# Stacja_Lutownicza_STM.net
KiCad netlist of a schematic drawn in EAGLE
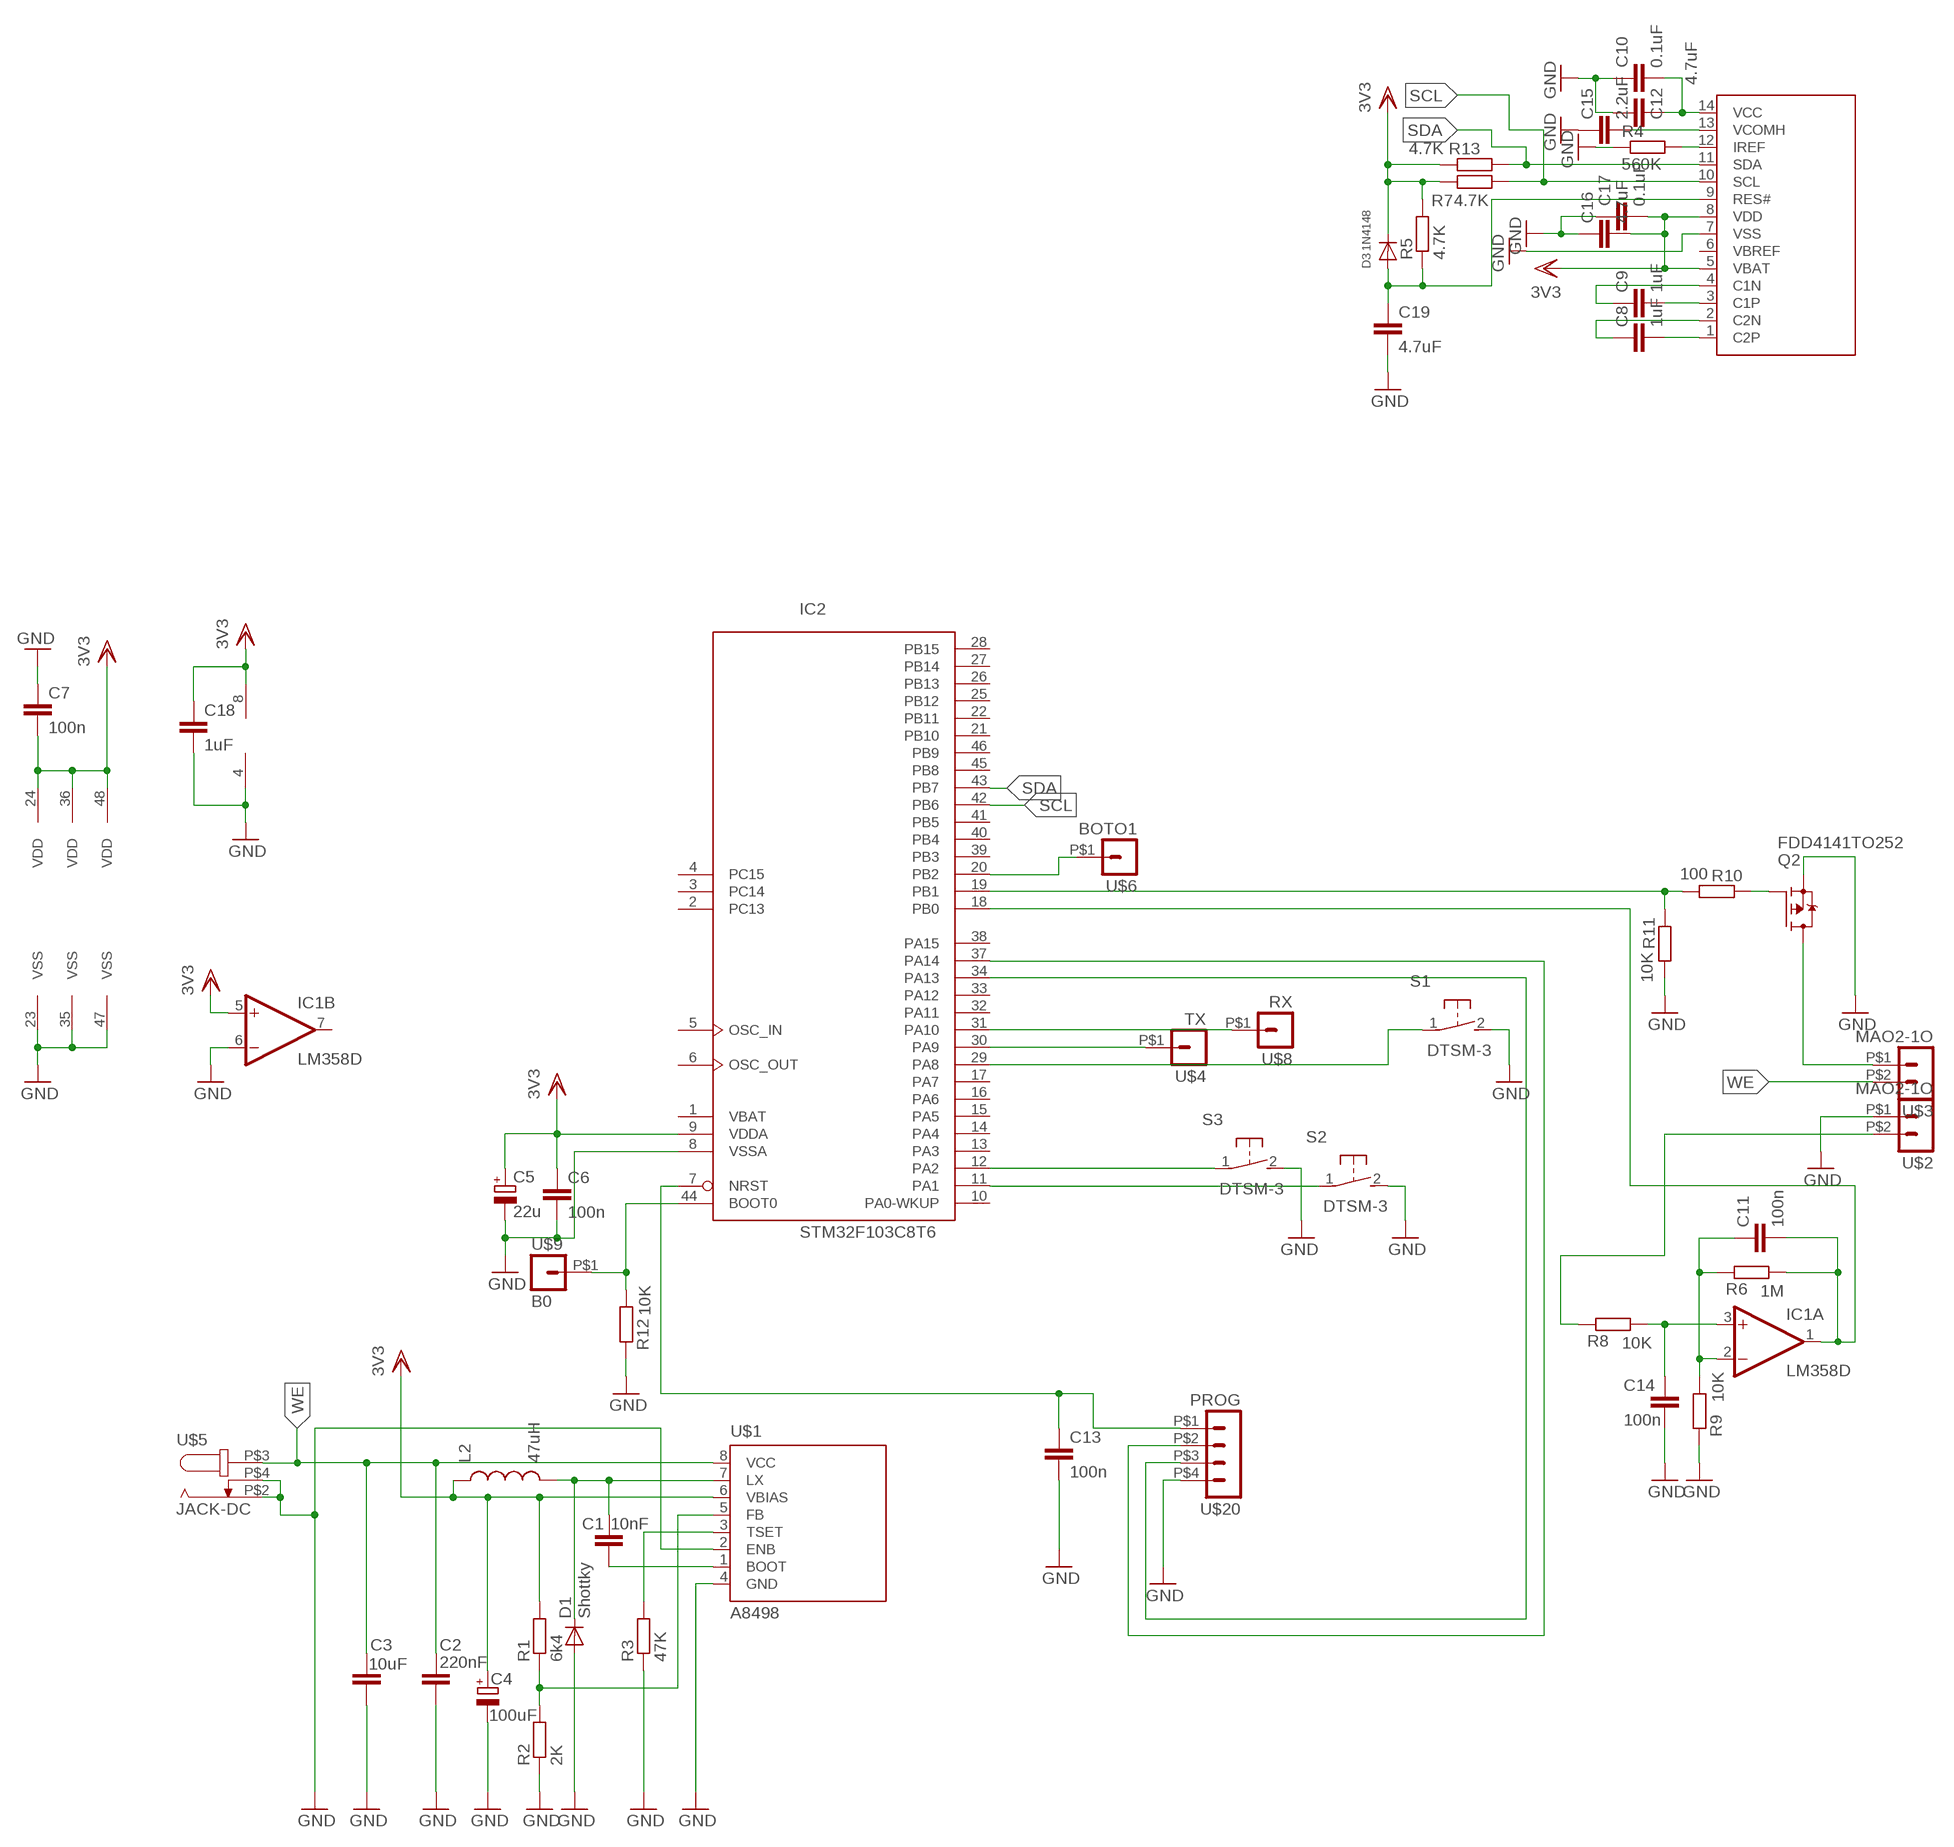
[diagram p0: schematic, sheet 1]

(export (version "E")
  (design (tool "Eeschema 10.0.6"))
  (components
    (comp (ref "C1")
      (value "10nF")
      (footprint "eagle-import:C1206")
      (libsource (lib "eagle-import") (part "C-EUC1206"))
    )
    (comp (ref "C2")
      (value "220nF")
      (footprint "eagle-import:C1210")
      (libsource (lib "eagle-import") (part "C-EUC1210"))
    )
    (comp (ref "C3")
      (value "10uF")
      (footprint "eagle-import:C0603")
      (libsource (lib "eagle-import") (part "C-EUC0603"))
    )
    (comp (ref "C4")
      (value "100uF")
      (footprint "eagle-import:SMC_D")
      (libsource (lib "eagle-import") (part "CPOL-EUSMCD"))
    )
    (comp (ref "C5")
      (value "22u")
      (footprint "eagle-import:R_2012-12R")
      (libsource (lib "eagle-import") (part "resistor_CPOL-EUR/2012-12R"))
    )
    (comp (ref "C6")
      (value "100n")
      (footprint "eagle-import:C0603")
      (libsource (lib "eagle-import") (part "resistor_C-EUC0603"))
    )
    (comp (ref "C7")
      (value "100n")
      (footprint "eagle-import:C0603")
      (libsource (lib "eagle-import") (part "resistor_C-EUC0603"))
    )
    (comp (ref "C8")
      (value "1uF")
      (footprint "eagle-import:C0603")
      (libsource (lib "eagle-import") (part "C-EUC0603"))
    )
    (comp (ref "C9")
      (value "1uF")
      (footprint "eagle-import:C0603")
      (libsource (lib "eagle-import") (part "C-EUC0603"))
    )
    (comp (ref "C10")
      (value "0.1uF")
      (footprint "eagle-import:C0603")
      (libsource (lib "eagle-import") (part "C-EUC0603"))
    )
    (comp (ref "C11")
      (value "100n")
      (footprint "eagle-import:C0603")
      (libsource (lib "eagle-import") (part "resistor_C-EUC0603"))
    )
    (comp (ref "C12")
      (value "4.7uF")
      (footprint "eagle-import:C0603")
      (libsource (lib "eagle-import") (part "C-EUC0603"))
    )
    (comp (ref "C13")
      (value "100n")
      (footprint "eagle-import:C0603")
      (libsource (lib "eagle-import") (part "resistor_C-EUC0603"))
    )
    (comp (ref "C14")
      (value "100n")
      (footprint "eagle-import:C0603")
      (libsource (lib "eagle-import") (part "resistor_C-EUC0603"))
    )
    (comp (ref "C15")
      (value "2.2uF")
      (footprint "eagle-import:C0603")
      (libsource (lib "eagle-import") (part "C-EUC0603"))
    )
    (comp (ref "C16")
      (value "4.7uF")
      (footprint "eagle-import:C0603")
      (libsource (lib "eagle-import") (part "C-EUC0603"))
    )
    (comp (ref "C17")
      (value "0.1uF")
      (footprint "eagle-import:C0603")
      (libsource (lib "eagle-import") (part "C-EUC0603"))
    )
    (comp (ref "C18")
      (value "1uF")
      (footprint "eagle-import:C0603")
      (libsource (lib "eagle-import") (part "C-EUC0603"))
    )
    (comp (ref "C19")
      (value "4.7uF")
      (footprint "eagle-import:C0603")
      (libsource (lib "eagle-import") (part "C-EUC0603"))
    )
    (comp (ref "D1")
      (value "Shottky")
      (footprint "eagle-import:SOD-123_MINI-SMA")
      (libsource (lib "eagle-import") (part "CGRM400-G3"))
    )
    (comp (ref "D3")
      (value "1N4148")
      (footprint "eagle-import:SOD-323F")
      (libsource (lib "eagle-import") (part "DIODESOD-323F"))
    )
    (comp (ref "IC1")
      (value "LM358D")
      (footprint "eagle-import:SO08")
      (libsource (lib "eagle-import") (part "LM358D"))
    )
    (comp (ref "IC2")
      (value "STM32F103C8T6")
      (footprint "eagle-import:LQFP48")
      (libsource (lib "eagle-import") (part "STM32F102CT4"))
    )
    (comp (ref "L2")
      (value "47uH")
      (footprint "eagle-import:INDUCTOR-1206")
      (libsource (lib "eagle-import") (part "INDUCTORH1206"))
    )
    (comp (ref "Q2")
      (value "FDD4141TO252")
      (footprint "eagle-import:TO252")
      (libsource (lib "eagle-import") (part "FDD4141TO252"))
    )
    (comp (ref "R1")
      (value "6k4")
      (footprint "eagle-import:R0603")
      (libsource (lib "eagle-import") (part "R-EU_R0603"))
    )
    (comp (ref "R2")
      (value "2K")
      (footprint "eagle-import:R0603")
      (libsource (lib "eagle-import") (part "R-EU_R0603"))
    )
    (comp (ref "R3")
      (value "47K")
      (footprint "eagle-import:R0603")
      (libsource (lib "eagle-import") (part "R-EU_R0603"))
    )
    (comp (ref "R4")
      (value "560K")
      (footprint "eagle-import:R0603")
      (libsource (lib "eagle-import") (part "R-EU_R0603"))
    )
    (comp (ref "R5")
      (value "4.7K")
      (footprint "eagle-import:R0603")
      (libsource (lib "eagle-import") (part "R-EU_R0603"))
    )
    (comp (ref "R6")
      (value "1M")
      (footprint "eagle-import:R0603")
      (libsource (lib "eagle-import") (part "R-EU_R0603"))
    )
    (comp (ref "R7")
      (value "4.7K")
      (footprint "eagle-import:R0603")
      (libsource (lib "eagle-import") (part "R-EU_R0603"))
    )
    (comp (ref "R8")
      (value "10K")
      (footprint "eagle-import:R0603")
      (libsource (lib "eagle-import") (part "R-EU_R0603"))
    )
    (comp (ref "R9")
      (value "10K")
      (footprint "eagle-import:R0603")
      (libsource (lib "eagle-import") (part "R-EU_R0603"))
    )
    (comp (ref "R10")
      (value "100")
      (footprint "eagle-import:R0603")
      (libsource (lib "eagle-import") (part "R-EU_R0603"))
    )
    (comp (ref "R11")
      (value "10K")
      (footprint "eagle-import:R0603")
      (libsource (lib "eagle-import") (part "R-EU_R0603"))
    )
    (comp (ref "R12")
      (value "10K")
      (footprint "eagle-import:R0603")
      (libsource (lib "eagle-import") (part "R-EU_R0603"))
    )
    (comp (ref "R13")
      (value "4.7K")
      (footprint "eagle-import:R0603")
      (libsource (lib "eagle-import") (part "R-EU_R0603"))
    )
    (comp (ref "S1")
      (value "DTSM-3")
      (footprint "eagle-import:DTSM-3")
      (libsource (lib "eagle-import") (part "DTSM-3"))
    )
    (comp (ref "S2")
      (value "DTSM-3")
      (footprint "eagle-import:DTSM-3")
      (libsource (lib "eagle-import") (part "DTSM-3"))
    )
    (comp (ref "S3")
      (value "DTSM-3")
      (footprint "eagle-import:DTSM-3")
      (libsource (lib "eagle-import") (part "DTSM-3"))
    )
    (comp (ref "U$1")
      (value "A8498")
      (footprint "eagle-import:SO08")
      (libsource (lib "eagle-import") (part "A8498"))
    )
    (comp (ref "U$2")
      (value "MAO2-1O")
      (footprint "eagle-import:MAO2-1O")
      (libsource (lib "eagle-import") (part "MAO2-1O"))
    )
    (comp (ref "U$3")
      (value "MAO2-1O")
      (footprint "eagle-import:MAO2-1O")
      (libsource (lib "eagle-import") (part "MAO2-1O"))
    )
    (comp (ref "U$4")
      (value "TX")
      (footprint "eagle-import:MAO1-1O")
      (libsource (lib "eagle-import") (part "MAO1-1O"))
    )
    (comp (ref "U$5")
      (value "JACK-DC")
      (footprint "eagle-import:JACK-DC")
      (libsource (lib "eagle-import") (part "JACK-DC"))
    )
    (comp (ref "U$6")
      (value "BOTO1")
      (footprint "eagle-import:MAO1-1O")
      (libsource (lib "eagle-import") (part "MAO1-1O"))
    )
    (comp (ref "U$7")
      (value "OLED_0_91")
      (footprint "eagle-import:OLED_0_91")
      (libsource (lib "eagle-import") (part "OLED_0_91"))
    )
    (comp (ref "U$8")
      (value "RX")
      (footprint "eagle-import:MAO1-1O")
      (libsource (lib "eagle-import") (part "MAO1-1O"))
    )
    (comp (ref "U$9")
      (value "B0")
      (footprint "eagle-import:MAO1-1O")
      (libsource (lib "eagle-import") (part "MAO1-1O"))
    )
    (comp (ref "U$20")
      (value "PROG")
      (footprint "eagle-import:MAO4-4O")
      (libsource (lib "eagle-import") (part "MAO4-$O"))
    )
  )
  (nets
    (net (code "1") (name "/VBAT") (class "Default")
      (node (ref "IC2") (pin "1") (pinfunction "VBAT_1") (pintype "power_in"))
    )
    (net (code "2") (name "3V3") (class "Default")
      (node (ref "C16") (pin "2") (pinfunction "2_2") (pintype "passive"))
      (node (ref "C17") (pin "2") (pinfunction "2_2") (pintype "passive"))
      (node (ref "C18") (pin "1") (pinfunction "1_1") (pintype "passive"))
      (node (ref "C4") (pin "+") (pinfunction "+_+") (pintype "passive"))
      (node (ref "C5") (pin "+") (pinfunction "+_+") (pintype "passive"))
      (node (ref "C6") (pin "1") (pinfunction "1_1") (pintype "passive"))
      (node (ref "C7") (pin "2") (pinfunction "2_2") (pintype "passive"))
      (node (ref "D3") (pin "C") (pinfunction "C_C") (pintype "passive"))
      (node (ref "IC1") (pin "5") (pinfunction "+IN_5") (pintype "input"))
      (node (ref "IC1") (pin "8") (pinfunction "V+_8") (pintype "power_in"))
      (node (ref "IC2") (pin "24") (pinfunction "VDD_24") (pintype "power_in"))
      (node (ref "IC2") (pin "36") (pinfunction "VDD_36") (pintype "power_in"))
      (node (ref "IC2") (pin "48") (pinfunction "VDD_48") (pintype "power_in"))
      (node (ref "IC2") (pin "9") (pinfunction "VDDA_9") (pintype "power_in"))
      (node (ref "L2") (pin "P$1") (pinfunction "1_P$1") (pintype "passive"))
      (node (ref "R1") (pin "2") (pinfunction "2_2") (pintype "passive"))
      (node (ref "R13") (pin "1") (pinfunction "1_1") (pintype "passive"))
      (node (ref "R5") (pin "2") (pinfunction "2_2") (pintype "passive"))
      (node (ref "R7") (pin "1") (pinfunction "1_1") (pintype "passive"))
      (node (ref "U$1") (pin "6") (pinfunction "VBIAS_6") (pintype "bidirectional"))
      (node (ref "U$7") (pin "5") (pinfunction "VBAT_5") (pintype "bidirectional"))
      (node (ref "U$7") (pin "8") (pinfunction "VDD_8") (pintype "bidirectional"))
    )
    (net (code "3") (name "GND") (class "Default")
      (node (ref "C10") (pin "1") (pinfunction "1_1") (pintype "passive"))
      (node (ref "C12") (pin "1") (pinfunction "1_1") (pintype "passive"))
      (node (ref "C13") (pin "2") (pinfunction "2_2") (pintype "passive"))
      (node (ref "C14") (pin "2") (pinfunction "2_2") (pintype "passive"))
      (node (ref "C15") (pin "1") (pinfunction "1_1") (pintype "passive"))
      (node (ref "C16") (pin "1") (pinfunction "1_1") (pintype "passive"))
      (node (ref "C17") (pin "1") (pinfunction "1_1") (pintype "passive"))
      (node (ref "C18") (pin "2") (pinfunction "2_2") (pintype "passive"))
      (node (ref "C19") (pin "2") (pinfunction "2_2") (pintype "passive"))
      (node (ref "C2") (pin "2") (pinfunction "2_2") (pintype "passive"))
      (node (ref "C3") (pin "2") (pinfunction "2_2") (pintype "passive"))
      (node (ref "C4") (pin "-") (pinfunction "-_-") (pintype "passive"))
      (node (ref "C5") (pin "-") (pinfunction "-_-") (pintype "passive"))
      (node (ref "C6") (pin "2") (pinfunction "2_2") (pintype "passive"))
      (node (ref "C7") (pin "1") (pinfunction "1_1") (pintype "passive"))
      (node (ref "D1") (pin "A") (pinfunction "A_A") (pintype "passive"))
      (node (ref "IC1") (pin "4") (pinfunction "V-_4") (pintype "power_in"))
      (node (ref "IC1") (pin "6") (pinfunction "-IN_6") (pintype "input"))
      (node (ref "IC2") (pin "23") (pinfunction "VSS_23") (pintype "power_in"))
      (node (ref "IC2") (pin "35") (pinfunction "VSS_35") (pintype "power_in"))
      (node (ref "IC2") (pin "47") (pinfunction "VSS_47") (pintype "power_in"))
      (node (ref "IC2") (pin "8") (pinfunction "VSSA_8") (pintype "power_in"))
      (node (ref "Q2") (pin "2") (pinfunction "S_2") (pintype "passive"))
      (node (ref "R11") (pin "2") (pinfunction "2_2") (pintype "passive"))
      (node (ref "R12") (pin "1") (pinfunction "1_1") (pintype "passive"))
      (node (ref "R2") (pin "1") (pinfunction "1_1") (pintype "passive"))
      (node (ref "R3") (pin "1") (pinfunction "1_1") (pintype "passive"))
      (node (ref "R4") (pin "1") (pinfunction "1_1") (pintype "passive"))
      (node (ref "R9") (pin "1") (pinfunction "1_1") (pintype "passive"))
      (node (ref "S1") (pin "2") (pinfunction "2_2") (pintype "passive"))
      (node (ref "S2") (pin "2") (pinfunction "2_2") (pintype "passive"))
      (node (ref "S3") (pin "2") (pinfunction "2_2") (pintype "passive"))
      (node (ref "U$1") (pin "2") (pinfunction "ENB_2") (pintype "bidirectional"))
      (node (ref "U$1") (pin "4") (pinfunction "GND_4") (pintype "power_in"))
      (node (ref "U$2") (pin "P$1") (pinfunction "1_P$1") (pintype "passive"))
      (node (ref "U$20") (pin "P$4") (pinfunction "4_P$4") (pintype "passive"))
      (node (ref "U$5") (pin "P$2") (pinfunction "1_P$2") (pintype "passive"))
      (node (ref "U$5") (pin "P$4") (pinfunction "2_P$4") (pintype "passive"))
      (node (ref "U$7") (pin "7") (pinfunction "VSS_7") (pintype "bidirectional"))
    )
    (net (code "4") (name "Net-(IC1A-+IN)") (class "Default")
      (node (ref "C14") (pin "1") (pinfunction "1_1") (pintype "passive"))
      (node (ref "IC1") (pin "3") (pinfunction "+IN_3") (pintype "input"))
      (node (ref "R8") (pin "2") (pinfunction "2_2") (pintype "passive"))
    )
    (net (code "5") (name "Net-(IC1A--IN)") (class "Default")
      (node (ref "C11") (pin "1") (pinfunction "1_1") (pintype "passive"))
      (node (ref "IC1") (pin "2") (pinfunction "-IN_2") (pintype "input"))
      (node (ref "R6") (pin "1") (pinfunction "1_1") (pintype "passive"))
      (node (ref "R9") (pin "2") (pinfunction "2_2") (pintype "passive"))
    )
    (net (code "6") (name "Net-(IC1A-OUT)") (class "Default")
      (node (ref "C11") (pin "2") (pinfunction "2_2") (pintype "passive"))
      (node (ref "IC1") (pin "1") (pinfunction "OUT_1") (pintype "output"))
      (node (ref "IC2") (pin "18") (pinfunction "PB0_18") (pintype "bidirectional"))
      (node (ref "R6") (pin "2") (pinfunction "2_2") (pintype "passive"))
    )
    (net (code "7") (name "Net-(IC2A-BOOT0)") (class "Default")
      (node (ref "IC2") (pin "44") (pinfunction "BOOT0_44") (pintype "input"))
      (node (ref "R12") (pin "2") (pinfunction "2_2") (pintype "passive"))
      (node (ref "U$9") (pin "P$1") (pinfunction "3_P$1") (pintype "passive"))
    )
    (net (code "8") (name "Net-(IC2A-NRST)") (class "Default")
      (node (ref "C13") (pin "1") (pinfunction "1_1") (pintype "passive"))
      (node (ref "IC2") (pin "7") (pinfunction "NRST_7") (pintype "bidirectional"))
      (node (ref "U$20") (pin "P$1") (pinfunction "1_P$1") (pintype "passive"))
    )
    (net (code "9") (name "Net-(IC2A-PA1)") (class "Default")
      (node (ref "IC2") (pin "11") (pinfunction "PA1_11") (pintype "bidirectional"))
      (node (ref "S2") (pin "1") (pinfunction "1_1") (pintype "passive"))
    )
    (net (code "10") (name "Net-(IC2A-PA2)") (class "Default")
      (node (ref "IC2") (pin "12") (pinfunction "PA2_12") (pintype "bidirectional"))
      (node (ref "S3") (pin "1") (pinfunction "1_1") (pintype "passive"))
    )
    (net (code "11") (name "Net-(IC2A-PA8)") (class "Default")
      (node (ref "IC2") (pin "29") (pinfunction "PA8_29") (pintype "bidirectional"))
      (node (ref "S1") (pin "1") (pinfunction "1_1") (pintype "passive"))
    )
    (net (code "12") (name "Net-(IC2A-PA9)") (class "Default")
      (node (ref "IC2") (pin "30") (pinfunction "PA9_30") (pintype "bidirectional"))
      (node (ref "U$4") (pin "P$1") (pinfunction "3_P$1") (pintype "passive"))
    )
    (net (code "13") (name "Net-(IC2A-PA10)") (class "Default")
      (node (ref "IC2") (pin "31") (pinfunction "PA10_31") (pintype "bidirectional"))
      (node (ref "U$8") (pin "P$1") (pinfunction "3_P$1") (pintype "passive"))
    )
    (net (code "14") (name "Net-(IC2A-PA13)") (class "Default")
      (node (ref "IC2") (pin "34") (pinfunction "PA13_34") (pintype "bidirectional"))
      (node (ref "U$20") (pin "P$3") (pinfunction "3_P$3") (pintype "passive"))
    )
    (net (code "15") (name "Net-(IC2A-PA14)") (class "Default")
      (node (ref "IC2") (pin "37") (pinfunction "PA14_37") (pintype "bidirectional"))
      (node (ref "U$20") (pin "P$2") (pinfunction "2_P$2") (pintype "passive"))
    )
    (net (code "16") (name "Net-(IC2A-PB1)") (class "Default")
      (node (ref "IC2") (pin "19") (pinfunction "PB1_19") (pintype "bidirectional"))
      (node (ref "R10") (pin "2") (pinfunction "2_2") (pintype "passive"))
      (node (ref "R11") (pin "1") (pinfunction "1_1") (pintype "passive"))
    )
    (net (code "17") (name "Net-(IC2A-PB2)") (class "Default")
      (node (ref "IC2") (pin "20") (pinfunction "PB2_20") (pintype "bidirectional"))
      (node (ref "U$6") (pin "P$1") (pinfunction "3_P$1") (pintype "passive"))
    )
    (net (code "18") (name "Net-(L2-2)") (class "Default")
      (node (ref "C1") (pin "2") (pinfunction "2_2") (pintype "passive"))
      (node (ref "D1") (pin "C") (pinfunction "C_C") (pintype "passive"))
      (node (ref "L2") (pin "P$2") (pinfunction "2_P$2") (pintype "passive"))
      (node (ref "U$1") (pin "7") (pinfunction "LX_7") (pintype "bidirectional"))
    )
    (net (code "19") (name "Net-(Q2-D)") (class "Default")
      (node (ref "Q2") (pin "3") (pinfunction "D_3") (pintype "passive"))
      (node (ref "U$3") (pin "P$1") (pinfunction "1_P$1") (pintype "passive"))
    )
    (net (code "20") (name "Net-(Q2-G)") (class "Default")
      (node (ref "Q2") (pin "1") (pinfunction "G_1") (pintype "passive"))
      (node (ref "R10") (pin "1") (pinfunction "1_1") (pintype "passive"))
    )
    (net (code "21") (name "Net-(U$1-BOOT)") (class "Default")
      (node (ref "C1") (pin "1") (pinfunction "1_1") (pintype "passive"))
      (node (ref "U$1") (pin "1") (pinfunction "BOOT_1") (pintype "bidirectional"))
    )
    (net (code "22") (name "Net-(U$1-FB)") (class "Default")
      (node (ref "R1") (pin "1") (pinfunction "1_1") (pintype "passive"))
      (node (ref "R2") (pin "2") (pinfunction "2_2") (pintype "passive"))
      (node (ref "U$1") (pin "5") (pinfunction "FB_5") (pintype "bidirectional"))
    )
    (net (code "23") (name "Net-(U$1-TSET)") (class "Default")
      (node (ref "R3") (pin "2") (pinfunction "2_2") (pintype "passive"))
      (node (ref "U$1") (pin "3") (pinfunction "TSET_3") (pintype "bidirectional"))
    )
    (net (code "24") (name "Net-(U$2-2)") (class "Default")
      (node (ref "R8") (pin "1") (pinfunction "1_1") (pintype "passive"))
      (node (ref "U$2") (pin "P$2") (pinfunction "2_P$2") (pintype "passive"))
    )
    (net (code "25") (name "Net-(U$7-C1N)") (class "Default")
      (node (ref "C9") (pin "1") (pinfunction "1_1") (pintype "passive"))
      (node (ref "U$7") (pin "4") (pinfunction "C1N_4") (pintype "bidirectional"))
    )
    (net (code "26") (name "Net-(U$7-C1P)") (class "Default")
      (node (ref "C9") (pin "2") (pinfunction "2_2") (pintype "passive"))
      (node (ref "U$7") (pin "3") (pinfunction "C1P_3") (pintype "bidirectional"))
    )
    (net (code "27") (name "Net-(U$7-C2N)") (class "Default")
      (node (ref "C8") (pin "1") (pinfunction "1_1") (pintype "passive"))
      (node (ref "U$7") (pin "2") (pinfunction "C2N_2") (pintype "bidirectional"))
    )
    (net (code "28") (name "Net-(U$7-C2P)") (class "Default")
      (node (ref "C8") (pin "2") (pinfunction "2_2") (pintype "passive"))
      (node (ref "U$7") (pin "1") (pinfunction "C2P_1") (pintype "bidirectional"))
    )
    (net (code "29") (name "Net-(U$7-IREF)") (class "Default")
      (node (ref "R4") (pin "2") (pinfunction "2_2") (pintype "passive"))
      (node (ref "U$7") (pin "12") (pinfunction "IREF_12") (pintype "bidirectional"))
    )
    (net (code "30") (name "Net-(U$7-RES#)") (class "Default")
      (node (ref "C19") (pin "1") (pinfunction "1_1") (pintype "passive"))
      (node (ref "D3") (pin "A") (pinfunction "A_A") (pintype "passive"))
      (node (ref "R5") (pin "1") (pinfunction "1_1") (pintype "passive"))
      (node (ref "U$7") (pin "9") (pinfunction "RES#_9") (pintype "bidirectional"))
    )
    (net (code "31") (name "Net-(U$7-VCC)") (class "Default")
      (node (ref "C10") (pin "2") (pinfunction "2_2") (pintype "passive"))
      (node (ref "C12") (pin "2") (pinfunction "2_2") (pintype "passive"))
      (node (ref "U$7") (pin "14") (pinfunction "VCC_14") (pintype "bidirectional"))
    )
    (net (code "32") (name "Net-(U$7-VCOMH)") (class "Default")
      (node (ref "C15") (pin "2") (pinfunction "2_2") (pintype "passive"))
      (node (ref "U$7") (pin "13") (pinfunction "VCOMH_13") (pintype "bidirectional"))
    )
    (net (code "33") (name "SCL") (class "Default")
      (node (ref "IC2") (pin "42") (pinfunction "PB6_42") (pintype "bidirectional"))
      (node (ref "R7") (pin "2") (pinfunction "2_2") (pintype "passive"))
      (node (ref "U$7") (pin "10") (pinfunction "SCL_10") (pintype "bidirectional"))
    )
    (net (code "34") (name "SDA") (class "Default")
      (node (ref "IC2") (pin "43") (pinfunction "PB7_43") (pintype "bidirectional"))
      (node (ref "R13") (pin "2") (pinfunction "2_2") (pintype "passive"))
      (node (ref "U$7") (pin "11") (pinfunction "SDA_11") (pintype "bidirectional"))
    )
    (net (code "35") (name "WE") (class "Default")
      (node (ref "C2") (pin "1") (pinfunction "1_1") (pintype "passive"))
      (node (ref "C3") (pin "1") (pinfunction "1_1") (pintype "passive"))
      (node (ref "U$1") (pin "8") (pinfunction "VCC_8") (pintype "power_in"))
      (node (ref "U$3") (pin "P$2") (pinfunction "2_P$2") (pintype "passive"))
      (node (ref "U$5") (pin "P$3") (pinfunction "3_P$3") (pintype "passive"))
    )
    (net (code "36") (name "unconnected-(IC1B-OUT-Pad7)") (class "Default")
      (node (ref "IC1") (pin "7") (pinfunction "OUT_7") (pintype "output"))
    )
    (net (code "37") (name "unconnected-(IC2A-OSC_IN-Pad5)") (class "Default")
      (node (ref "IC2") (pin "5") (pinfunction "OSC_IN_5") (pintype "bidirectional"))
    )
    (net (code "38") (name "unconnected-(IC2A-OSC_OUT-Pad6)") (class "Default")
      (node (ref "IC2") (pin "6") (pinfunction "OSC_OUT_6") (pintype "bidirectional"))
    )
    (net (code "39") (name "unconnected-(IC2A-PA0-WKUP-Pad10)") (class "Default")
      (node (ref "IC2") (pin "10") (pinfunction "PA0-WKUP_10") (pintype "bidirectional"))
    )
    (net (code "40") (name "unconnected-(IC2A-PA3-Pad13)") (class "Default")
      (node (ref "IC2") (pin "13") (pinfunction "PA3_13") (pintype "bidirectional"))
    )
    (net (code "41") (name "unconnected-(IC2A-PA4-Pad14)") (class "Default")
      (node (ref "IC2") (pin "14") (pinfunction "PA4_14") (pintype "bidirectional"))
    )
    (net (code "42") (name "unconnected-(IC2A-PA5-Pad15)") (class "Default")
      (node (ref "IC2") (pin "15") (pinfunction "PA5_15") (pintype "bidirectional"))
    )
    (net (code "43") (name "unconnected-(IC2A-PA6-Pad16)") (class "Default")
      (node (ref "IC2") (pin "16") (pinfunction "PA6_16") (pintype "bidirectional"))
    )
    (net (code "44") (name "unconnected-(IC2A-PA7-Pad17)") (class "Default")
      (node (ref "IC2") (pin "17") (pinfunction "PA7_17") (pintype "bidirectional"))
    )
    (net (code "45") (name "unconnected-(IC2A-PA11-Pad32)") (class "Default")
      (node (ref "IC2") (pin "32") (pinfunction "PA11_32") (pintype "bidirectional"))
    )
    (net (code "46") (name "unconnected-(IC2A-PA12-Pad33)") (class "Default")
      (node (ref "IC2") (pin "33") (pinfunction "PA12_33") (pintype "bidirectional"))
    )
    (net (code "47") (name "unconnected-(IC2A-PA15-Pad38)") (class "Default")
      (node (ref "IC2") (pin "38") (pinfunction "PA15_38") (pintype "bidirectional"))
    )
    (net (code "48") (name "unconnected-(IC2A-PB3-Pad39)") (class "Default")
      (node (ref "IC2") (pin "39") (pinfunction "PB3_39") (pintype "bidirectional"))
    )
    (net (code "49") (name "unconnected-(IC2A-PB4-Pad40)") (class "Default")
      (node (ref "IC2") (pin "40") (pinfunction "PB4_40") (pintype "bidirectional"))
    )
    (net (code "50") (name "unconnected-(IC2A-PB5-Pad41)") (class "Default")
      (node (ref "IC2") (pin "41") (pinfunction "PB5_41") (pintype "bidirectional"))
    )
    (net (code "51") (name "unconnected-(IC2A-PB8-Pad45)") (class "Default")
      (node (ref "IC2") (pin "45") (pinfunction "PB8_45") (pintype "bidirectional"))
    )
    (net (code "52") (name "unconnected-(IC2A-PB9-Pad46)") (class "Default")
      (node (ref "IC2") (pin "46") (pinfunction "PB9_46") (pintype "bidirectional"))
    )
    (net (code "53") (name "unconnected-(IC2A-PB10-Pad21)") (class "Default")
      (node (ref "IC2") (pin "21") (pinfunction "PB10_21") (pintype "bidirectional"))
    )
    (net (code "54") (name "unconnected-(IC2A-PB11-Pad22)") (class "Default")
      (node (ref "IC2") (pin "22") (pinfunction "PB11_22") (pintype "bidirectional"))
    )
    (net (code "55") (name "unconnected-(IC2A-PB12-Pad25)") (class "Default")
      (node (ref "IC2") (pin "25") (pinfunction "PB12_25") (pintype "bidirectional"))
    )
    (net (code "56") (name "unconnected-(IC2A-PB13-Pad26)") (class "Default")
      (node (ref "IC2") (pin "26") (pinfunction "PB13_26") (pintype "bidirectional"))
    )
    (net (code "57") (name "unconnected-(IC2A-PB14-Pad27)") (class "Default")
      (node (ref "IC2") (pin "27") (pinfunction "PB14_27") (pintype "bidirectional"))
    )
    (net (code "58") (name "unconnected-(IC2A-PB15-Pad28)") (class "Default")
      (node (ref "IC2") (pin "28") (pinfunction "PB15_28") (pintype "bidirectional"))
    )
    (net (code "59") (name "unconnected-(IC2A-PC13-Pad2)") (class "Default")
      (node (ref "IC2") (pin "2") (pinfunction "PC13_2") (pintype "bidirectional"))
    )
    (net (code "60") (name "unconnected-(IC2A-PC14-Pad3)") (class "Default")
      (node (ref "IC2") (pin "3") (pinfunction "PC14_3") (pintype "bidirectional"))
    )
    (net (code "61") (name "unconnected-(IC2A-PC15-Pad4)") (class "Default")
      (node (ref "IC2") (pin "4") (pinfunction "PC15_4") (pintype "bidirectional"))
    )
    (net (code "62") (name "unconnected-(U$7-VBREF-Pad6)") (class "Default")
      (node (ref "U$7") (pin "6") (pinfunction "VBREF_6") (pintype "bidirectional"))
    )
  )
)
